# Sheet1.net
KiCad netlist of a schematic drawn in Altium Designer
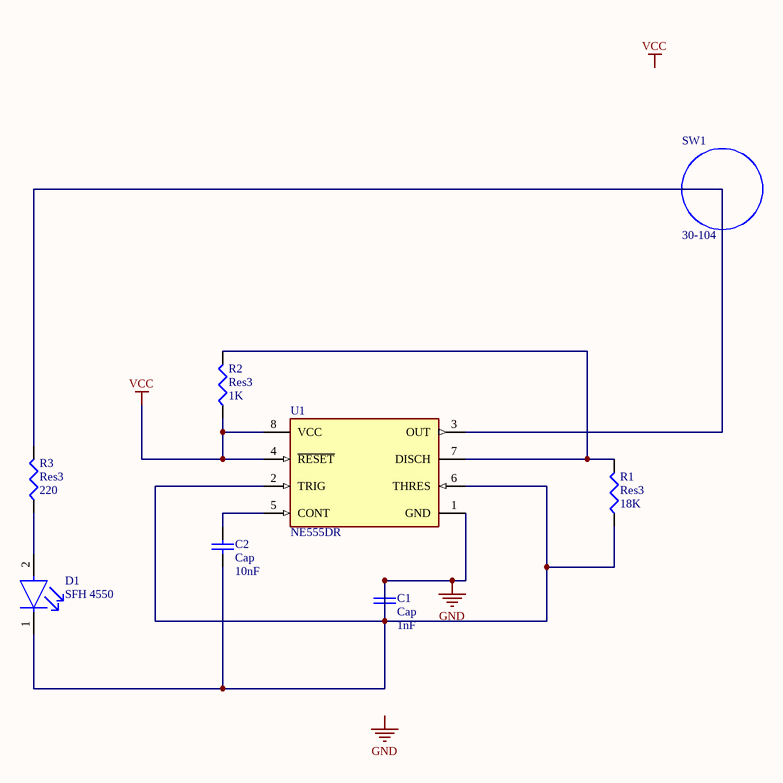
[diagram p0: Sheet1.SchDoc]

(export (version "E")
  (design (tool "Eeschema 10.0.6"))
  (components
    (comp (ref "C1")
      (value "Cap")
      (footprint "RAD-0.3")
      (description "Capacitor")
      (fields (field (name "ALTIUM_VALUE") "1nF") (field (name "PUBLISHER") "Altium Limited"))
      (libsource (lib "Miscellaneous Devices") (part "Cap"))
    )
    (comp (ref "C2")
      (value "Cap")
      (footprint "RAD-0.3")
      (description "Capacitor")
      (fields (field (name "ALTIUM_VALUE") "10nF") (field (name "PUBLISHER") "Altium Limited"))
      (libsource (lib "Miscellaneous Devices") (part "Cap"))
    )
    (comp (ref "D1")
      (value "SFH 4550")
      (footprint "FP-SFH_4550-MFG")
      (description "EMITTER IR 860NM 100MA RADIAL")
      (fields
        (field (name "OCTOPART") "https://octopart.com/sfh+4550-osram+opto-55410894")
        (field (name "MANUFACTURER") "Osram Opto")
      )
      (libsource (lib "Altium Content Vault") (part "75a0115997dd6a71327e26aab64f6f8"))
    )
    (comp (ref "R1")
      (value "Res3")
      (footprint "J1-0603")
      (description "Resistor")
      (fields (field (name "ALTIUM_VALUE") "18K") (field (name "PUBLISHER") "Altium Limited"))
      (libsource (lib "Miscellaneous Devices") (part "Res3"))
    )
    (comp (ref "R2")
      (value "Res3")
      (footprint "J1-0603")
      (description "Resistor")
      (fields (field (name "ALTIUM_VALUE") "1K") (field (name "PUBLISHER") "Altium Limited"))
      (libsource (lib "Miscellaneous Devices") (part "Res3"))
    )
    (comp (ref "R3")
      (value "Res3")
      (footprint "J1-0603")
      (description "Resistor")
      (fields (field (name "ALTIUM_VALUE") "220") (field (name "PUBLISHER") "Altium Limited"))
      (libsource (lib "Miscellaneous Devices") (part "Res3"))
    )
    (comp (ref "SW1")
      (value "30-104")
      (footprint "FP-30-104-MFG")
      (description "SWITCH PUSH SPST-NO 0.15A 24V")
      (libsource (lib "Altium Content Vault") (part "fa792097c1d5a57a286b5bc13786274"))
    )
    (comp (ref "U1")
      (value "NE555DR")
      (footprint "FP-D0008A-IPC_A")
      (description "IC OSC SGL TIMER 100KHZ 8-SOIC")
      (libsource (lib "Altium Content Vault") (part "a29bba90211dec1890110b94dad7d53"))
    )
  )
  (nets
    (net (code "1") (name "GND") (class "Default")
      (node (ref "C1") (pin "1") (pinfunction "1_1") (pintype "passive"))
      (node (ref "C1") (pin "2") (pinfunction "2_2") (pintype "passive"))
      (node (ref "C2") (pin "1") (pinfunction "1_1") (pintype "passive"))
      (node (ref "D1") (pin "1") (pinfunction "C_1") (pintype "passive"))
      (node (ref "R1") (pin "1") (pinfunction "1_1") (pintype "passive"))
      (node (ref "U1") (pin "1") (pinfunction "GND_1") (pintype "power_in"))
      (node (ref "U1") (pin "2") (pinfunction "TRIG_2") (pintype "input"))
      (node (ref "U1") (pin "6") (pinfunction "THRES_6") (pintype "input"))
    )
    (net (code "2") (name "Net-(D1-A)") (class "Default")
      (node (ref "D1") (pin "2") (pinfunction "A_2") (pintype "passive"))
      (node (ref "R3") (pin "1") (pinfunction "1_1") (pintype "passive"))
    )
    (net (code "3") (name "Net-(U1-CONT)") (class "Default")
      (node (ref "C2") (pin "2") (pinfunction "2_2") (pintype "passive"))
      (node (ref "U1") (pin "5") (pinfunction "CONT_5") (pintype "input"))
    )
    (net (code "4") (name "Net-(U1-DISCH)") (class "Default")
      (node (ref "R1") (pin "2") (pinfunction "2_2") (pintype "passive"))
      (node (ref "R2") (pin "2") (pinfunction "2_2") (pintype "passive"))
      (node (ref "U1") (pin "7") (pinfunction "DISCH_7") (pintype "open_collector"))
    )
    (net (code "5") (name "Net-(U1-OUT)") (class "Default")
      (node (ref "R3") (pin "2") (pinfunction "2_2") (pintype "passive"))
      (node (ref "U1") (pin "3") (pinfunction "OUT_3") (pintype "output"))
    )
    (net (code "6") (name "VCC") (class "Default")
      (node (ref "R2") (pin "1") (pinfunction "1_1") (pintype "passive"))
      (node (ref "U1") (pin "4") (pinfunction "~{RESET}_4") (pintype "input"))
      (node (ref "U1") (pin "8") (pinfunction "VCC_8") (pintype "power_in"))
    )
  )
)
